# ArduinoUNOGamePlatform.net
KiCad netlist of a schematic drawn in EAGLE
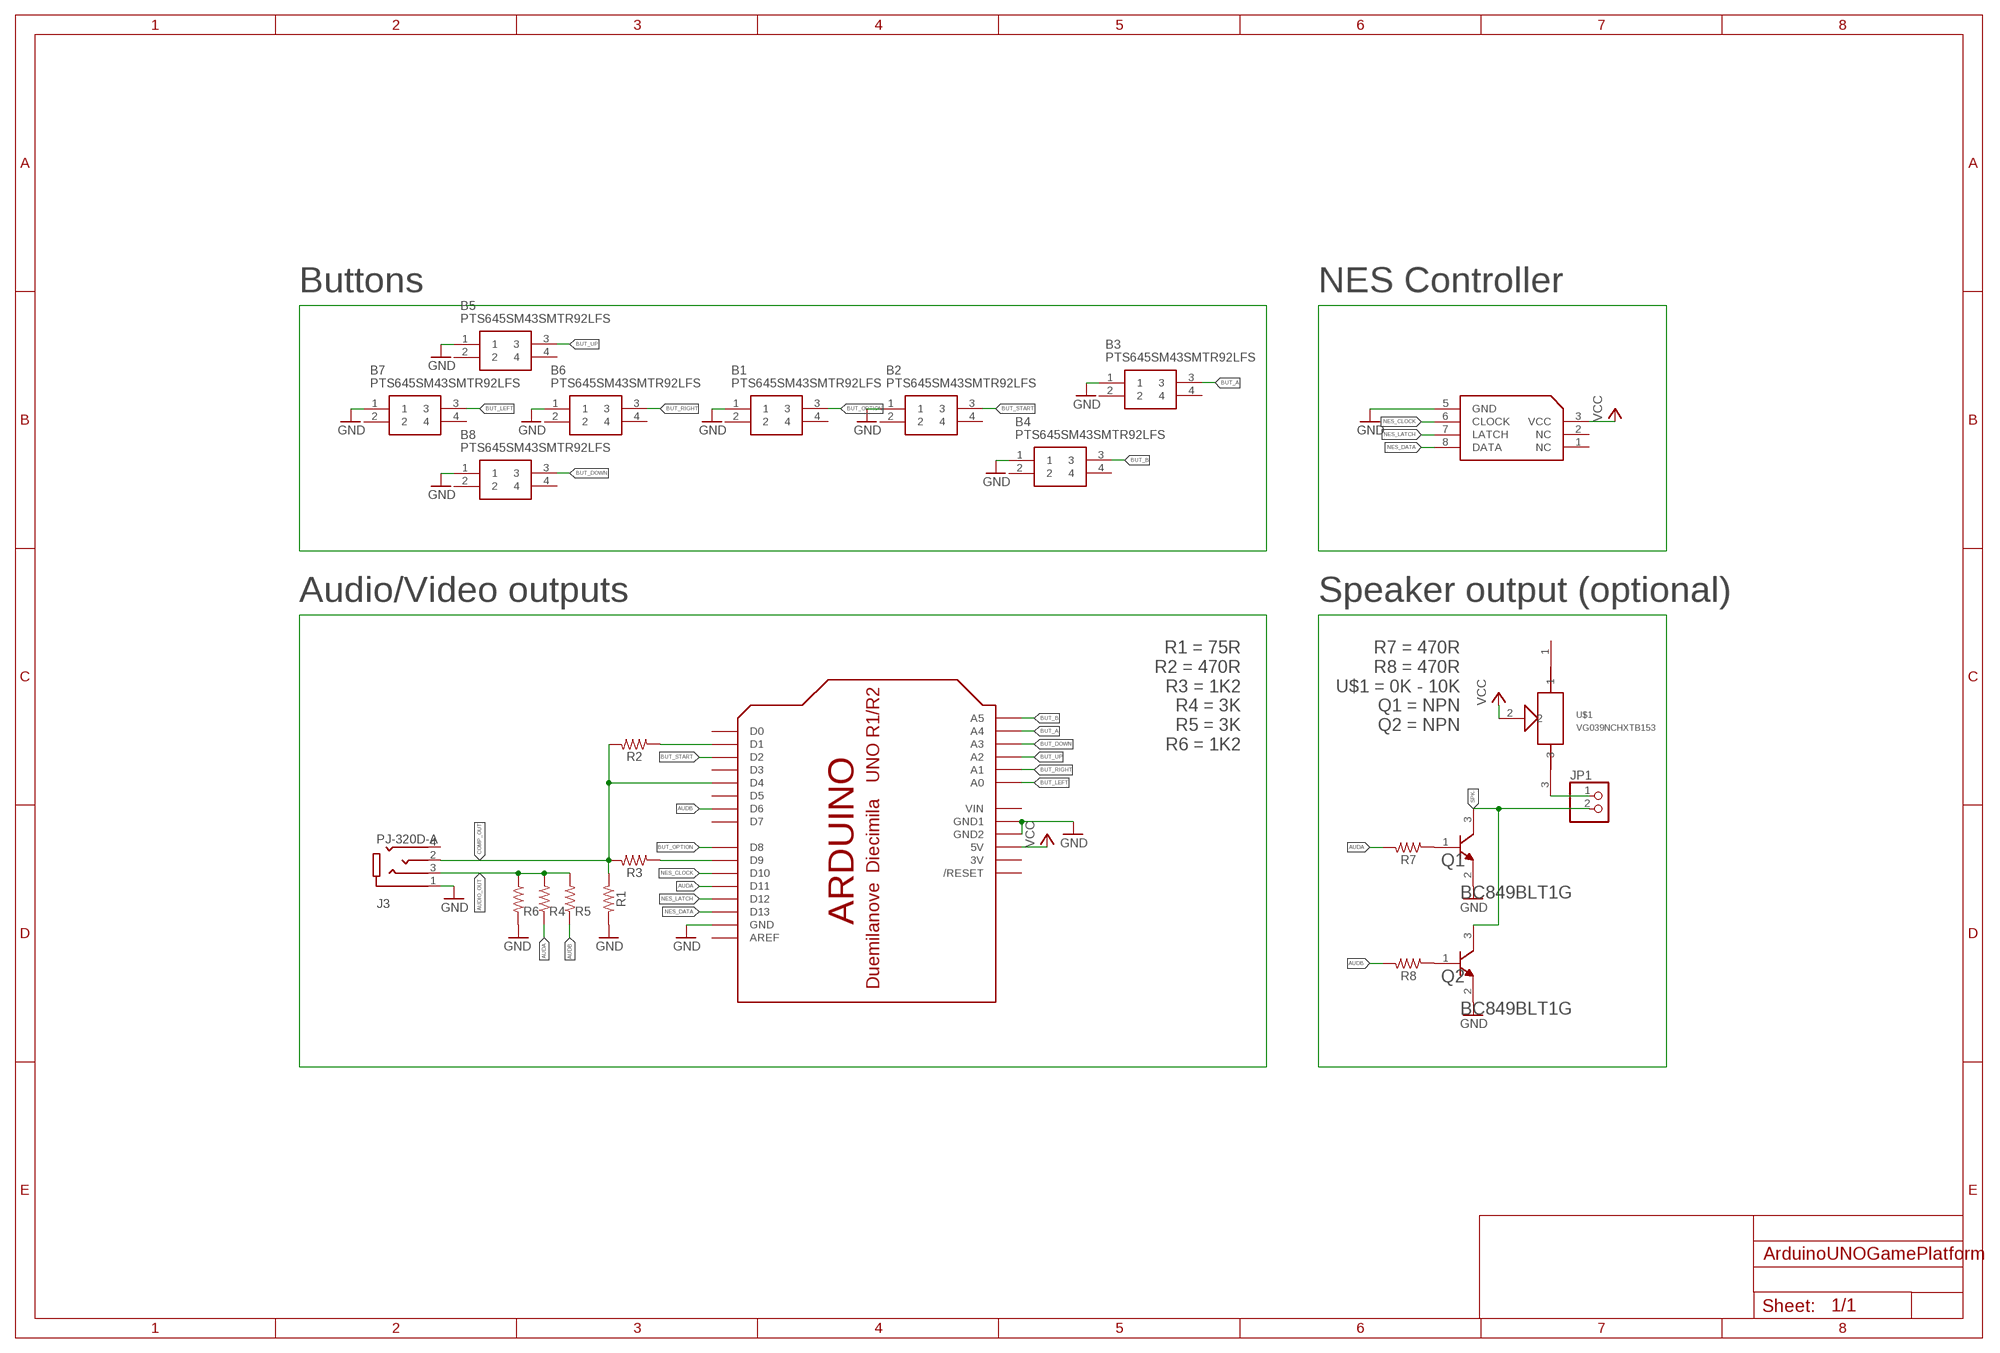
[diagram p0: schematic, sheet 1]

(export (version "E")
  (design (tool "Eeschema 10.0.6"))
  (components
    (comp (ref "B1")
      (value "PTS645SM43SMTR92LFS")
      (footprint "eagle-import:PTS645(SMT)")
      (fields (field (name "MOUSER_PART_NUMBER") "611-PTS645SM43SMTR92"))
      (libsource (lib "eagle-import") (part "PTS645SM43SMTR92LFS"))
    )
    (comp (ref "B2")
      (value "PTS645SM43SMTR92LFS")
      (footprint "eagle-import:PTS645(SMT)")
      (fields (field (name "MOUSER_PART_NUMBER") "611-PTS645SM43SMTR92"))
      (libsource (lib "eagle-import") (part "PTS645SM43SMTR92LFS"))
    )
    (comp (ref "B3")
      (value "PTS645SM43SMTR92LFS")
      (footprint "eagle-import:PTS645(SMT)")
      (fields (field (name "MOUSER_PART_NUMBER") "611-PTS645SM43SMTR92"))
      (libsource (lib "eagle-import") (part "PTS645SM43SMTR92LFS"))
    )
    (comp (ref "B4")
      (value "PTS645SM43SMTR92LFS")
      (footprint "eagle-import:PTS645(SMT)")
      (fields (field (name "MOUSER_PART_NUMBER") "611-PTS645SM43SMTR92"))
      (libsource (lib "eagle-import") (part "PTS645SM43SMTR92LFS"))
    )
    (comp (ref "B5")
      (value "PTS645SM43SMTR92LFS")
      (footprint "eagle-import:PTS645(SMT)")
      (fields (field (name "MOUSER_PART_NUMBER") "611-PTS645SM43SMTR92"))
      (libsource (lib "eagle-import") (part "PTS645SM43SMTR92LFS"))
    )
    (comp (ref "B6")
      (value "PTS645SM43SMTR92LFS")
      (footprint "eagle-import:PTS645(SMT)")
      (fields (field (name "MOUSER_PART_NUMBER") "611-PTS645SM43SMTR92"))
      (libsource (lib "eagle-import") (part "PTS645SM43SMTR92LFS"))
    )
    (comp (ref "B7")
      (value "PTS645SM43SMTR92LFS")
      (footprint "eagle-import:PTS645(SMT)")
      (fields (field (name "MOUSER_PART_NUMBER") "611-PTS645SM43SMTR92"))
      (libsource (lib "eagle-import") (part "PTS645SM43SMTR92LFS"))
    )
    (comp (ref "B8")
      (value "PTS645SM43SMTR92LFS")
      (footprint "eagle-import:PTS645(SMT)")
      (fields (field (name "MOUSER_PART_NUMBER") "611-PTS645SM43SMTR92"))
      (libsource (lib "eagle-import") (part "PTS645SM43SMTR92LFS"))
    )
    (comp (ref "J3")
      (value "PJ-320D-A")
      (footprint "eagle-import:HRO_PJ-320D-A")
      (fields (field (name "MF") "HRO Electronics Co., Ltd."))
      (libsource (lib "eagle-import") (part "PJ-320D-A"))
    )
    (comp (ref "JP1")
      (value "PINHD-1X2")
      (footprint "eagle-import:1X02")
      (libsource (lib "eagle-import") (part "PINHD-1X2"))
    )
    (comp (ref "Q1")
      (value "ON_SEMICONDUCTOR_BC849BLT1GON_SEMICONDUCTOR_BC849BLT1G_0_0")
      (footprint "eagle-import:ON_SEMICONDUCTOR_BC849BLT1G_0")
      (fields (field (name "MF") "On Semiconductor") (field (name "MPN") "BC849BLT1G"))
      (libsource (lib "eagle-import") (part "ON_SEMICONDUCTOR_BC849BLT1GON_SEMICONDUCTOR_BC849BLT1G_0_0"))
    )
    (comp (ref "Q2")
      (value "ON_SEMICONDUCTOR_BC849BLT1GON_SEMICONDUCTOR_BC849BLT1G_0_0")
      (footprint "eagle-import:ON_SEMICONDUCTOR_BC849BLT1G_0")
      (fields (field (name "MF") "On Semiconductor") (field (name "MPN") "BC849BLT1G"))
      (libsource (lib "eagle-import") (part "ON_SEMICONDUCTOR_BC849BLT1GON_SEMICONDUCTOR_BC849BLT1G_0_0"))
    )
    (comp (ref "R1")
      (value "75R")
      (footprint "eagle-import:52101-101-REV-A_RC-MASTER-SMD_R0603MP")
      (libsource (lib "eagle-import") (part "52101-101-REV-A_RC-MASTER-SMD_R_0603MP"))
    )
    (comp (ref "R2")
      (value "220R")
      (footprint "eagle-import:52101-101-REV-A_RC-MASTER-SMD_R0603MP")
      (libsource (lib "eagle-import") (part "52101-101-REV-A_RC-MASTER-SMD_R_0603MP"))
    )
    (comp (ref "R3")
      (value "1K2")
      (footprint "eagle-import:52101-101-REV-A_RC-MASTER-SMD_R0603MP")
      (libsource (lib "eagle-import") (part "52101-101-REV-A_RC-MASTER-SMD_R_0603MP"))
    )
    (comp (ref "R4")
      (value "3K")
      (footprint "eagle-import:52101-101-REV-A_RC-MASTER-SMD_R0603MP")
      (libsource (lib "eagle-import") (part "52101-101-REV-A_RC-MASTER-SMD_R_0603MP"))
    )
    (comp (ref "R5")
      (value "3K")
      (footprint "eagle-import:52101-101-REV-A_RC-MASTER-SMD_R0603MP")
      (libsource (lib "eagle-import") (part "52101-101-REV-A_RC-MASTER-SMD_R_0603MP"))
    )
    (comp (ref "R6")
      (value "1K2")
      (footprint "eagle-import:52101-101-REV-A_RC-MASTER-SMD_R0603MP")
      (libsource (lib "eagle-import") (part "52101-101-REV-A_RC-MASTER-SMD_R_0603MP"))
    )
    (comp (ref "R7")
      (value "470R")
      (footprint "eagle-import:52101-101-REV-A_RC-MASTER-SMD_R0603MP")
      (libsource (lib "eagle-import") (part "52101-101-REV-A_RC-MASTER-SMD_R_0603MP"))
    )
    (comp (ref "R8")
      (value "470R")
      (footprint "eagle-import:52101-101-REV-A_RC-MASTER-SMD_R0603MP")
      (libsource (lib "eagle-import") (part "52101-101-REV-A_RC-MASTER-SMD_R_0603MP"))
    )
    (comp (ref "U$1")
      (value "VG039NCHXTB153")
      (footprint "eagle-import:VG039NCHXTB101")
      (libsource (lib "eagle-import") (part "VG039NCHXTB153"))
    )
    (comp (ref "U$2")
      (value "ARDUINO-BPLACE")
      (footprint "eagle-import:ARDUINO-BPLACE")
      (libsource (lib "eagle-import") (part "ARDUINO-BPLACE"))
    )
    (comp (ref "U$3")
      (value "NES-CONTROLLER-PORT")
      (footprint "eagle-import:NES-CONTROLLER-SOCKET")
      (libsource (lib "eagle-import") (part "NES-CONTROLLER-PORT"))
    )
  )
  (nets
    (net (code "1") (name "/3V") (class "Default")
      (node (ref "U$2") (pin "3V") (pinfunction "3V_3V") (pintype "power_in"))
    )
    (net (code "2") (name "/VIN") (class "Default")
      (node (ref "U$2") (pin "VIN") (pinfunction "VIN_VIN") (pintype "power_in"))
    )
    (net (code "3") (name "AUDA") (class "Default")
      (node (ref "R4") (pin "1") (pinfunction "1_1") (pintype "passive"))
      (node (ref "R7") (pin "2") (pinfunction "2_2") (pintype "passive"))
      (node (ref "U$2") (pin "D11") (pinfunction "D11_D11") (pintype "bidirectional"))
    )
    (net (code "4") (name "AUDB") (class "Default")
      (node (ref "R5") (pin "1") (pinfunction "1_1") (pintype "passive"))
      (node (ref "R8") (pin "2") (pinfunction "2_2") (pintype "passive"))
      (node (ref "U$2") (pin "D6") (pinfunction "D6_D6") (pintype "bidirectional"))
    )
    (net (code "5") (name "AUDIO_OUT") (class "Default")
      (node (ref "J3") (pin "3") (pinfunction "RING1_3") (pintype "passive"))
      (node (ref "R4") (pin "2") (pinfunction "2_2") (pintype "passive"))
      (node (ref "R5") (pin "2") (pinfunction "2_2") (pintype "passive"))
      (node (ref "R6") (pin "1") (pinfunction "1_1") (pintype "passive"))
    )
    (net (code "6") (name "BUT_A") (class "Default")
      (node (ref "B3") (pin "3") (pinfunction "3_3") (pintype "bidirectional"))
      (node (ref "U$2") (pin "A4") (pinfunction "A4_A4") (pintype "bidirectional"))
    )
    (net (code "7") (name "BUT_B") (class "Default")
      (node (ref "B4") (pin "3") (pinfunction "3_3") (pintype "bidirectional"))
      (node (ref "U$2") (pin "A5") (pinfunction "A5_A5") (pintype "bidirectional"))
    )
    (net (code "8") (name "BUT_DOWN") (class "Default")
      (node (ref "B8") (pin "3") (pinfunction "3_3") (pintype "bidirectional"))
      (node (ref "U$2") (pin "A3") (pinfunction "A3_A3") (pintype "bidirectional"))
    )
    (net (code "9") (name "BUT_LEFT") (class "Default")
      (node (ref "B7") (pin "3") (pinfunction "3_3") (pintype "bidirectional"))
      (node (ref "U$2") (pin "A0") (pinfunction "A0_A0") (pintype "bidirectional"))
    )
    (net (code "10") (name "BUT_OPTION") (class "Default")
      (node (ref "B1") (pin "3") (pinfunction "3_3") (pintype "bidirectional"))
      (node (ref "U$2") (pin "D8") (pinfunction "D8_D8") (pintype "bidirectional"))
    )
    (net (code "11") (name "BUT_RIGHT") (class "Default")
      (node (ref "B6") (pin "3") (pinfunction "3_3") (pintype "bidirectional"))
      (node (ref "U$2") (pin "A1") (pinfunction "A1_A1") (pintype "bidirectional"))
    )
    (net (code "12") (name "BUT_START") (class "Default")
      (node (ref "B2") (pin "3") (pinfunction "3_3") (pintype "bidirectional"))
      (node (ref "U$2") (pin "D2") (pinfunction "D2_D2") (pintype "bidirectional"))
    )
    (net (code "13") (name "BUT_UP") (class "Default")
      (node (ref "B5") (pin "3") (pinfunction "3_3") (pintype "bidirectional"))
      (node (ref "U$2") (pin "A2") (pinfunction "A2_A2") (pintype "bidirectional"))
    )
    (net (code "14") (name "COMP_OUT") (class "Default")
      (node (ref "J3") (pin "2") (pinfunction "TIP_2") (pintype "passive"))
      (node (ref "R1") (pin "1") (pinfunction "1_1") (pintype "passive"))
      (node (ref "R2") (pin "2") (pinfunction "2_2") (pintype "passive"))
      (node (ref "R3") (pin "2") (pinfunction "2_2") (pintype "passive"))
      (node (ref "U$2") (pin "D4") (pinfunction "D4_D4") (pintype "bidirectional"))
    )
    (net (code "15") (name "GND") (class "Default")
      (node (ref "B1") (pin "1") (pinfunction "1_1") (pintype "bidirectional"))
      (node (ref "B2") (pin "1") (pinfunction "1_1") (pintype "bidirectional"))
      (node (ref "B3") (pin "1") (pinfunction "1_1") (pintype "bidirectional"))
      (node (ref "B4") (pin "1") (pinfunction "1_1") (pintype "bidirectional"))
      (node (ref "B5") (pin "1") (pinfunction "1_1") (pintype "bidirectional"))
      (node (ref "B6") (pin "1") (pinfunction "1_1") (pintype "bidirectional"))
      (node (ref "B7") (pin "1") (pinfunction "1_1") (pintype "bidirectional"))
      (node (ref "B8") (pin "1") (pinfunction "1_1") (pintype "bidirectional"))
      (node (ref "J3") (pin "1") (pinfunction "SLEEVE_1") (pintype "passive"))
      (node (ref "Q1") (pin "2") (pinfunction "E_2") (pintype "passive"))
      (node (ref "Q2") (pin "2") (pinfunction "E_2") (pintype "passive"))
      (node (ref "R1") (pin "2") (pinfunction "2_2") (pintype "passive"))
      (node (ref "R6") (pin "2") (pinfunction "2_2") (pintype "passive"))
      (node (ref "U$2") (pin "GND") (pinfunction "GND_GND") (pintype "power_in"))
      (node (ref "U$2") (pin "GND1") (pinfunction "GND1_GND1") (pintype "power_in"))
      (node (ref "U$2") (pin "GND2") (pinfunction "GND2_GND2") (pintype "power_in"))
      (node (ref "U$3") (pin "5") (pinfunction "GND_5") (pintype "bidirectional"))
    )
    (net (code "16") (name "NES_CLOCK") (class "Default")
      (node (ref "U$2") (pin "D10") (pinfunction "D10_D10") (pintype "bidirectional"))
      (node (ref "U$3") (pin "6") (pinfunction "CLOCK_6") (pintype "bidirectional"))
    )
    (net (code "17") (name "NES_DATA") (class "Default")
      (node (ref "U$2") (pin "D13") (pinfunction "D13_D13") (pintype "bidirectional"))
      (node (ref "U$3") (pin "8") (pinfunction "DATA_8") (pintype "bidirectional"))
    )
    (net (code "18") (name "NES_LATCH") (class "Default")
      (node (ref "U$2") (pin "D12") (pinfunction "D12_D12") (pintype "bidirectional"))
      (node (ref "U$3") (pin "7") (pinfunction "LATCH_7") (pintype "bidirectional"))
    )
    (net (code "19") (name "Net-(JP1-Pad1)") (class "Default")
      (node (ref "JP1") (pin "1") (pinfunction "1_1") (pintype "passive"))
      (node (ref "U$1") (pin "3") (pinfunction "3_3") (pintype "bidirectional"))
    )
    (net (code "20") (name "Net-(Q1-B)") (class "Default")
      (node (ref "Q1") (pin "1") (pinfunction "B_1") (pintype "passive"))
      (node (ref "R7") (pin "1") (pinfunction "1_1") (pintype "passive"))
    )
    (net (code "21") (name "Net-(Q2-B)") (class "Default")
      (node (ref "Q2") (pin "1") (pinfunction "B_1") (pintype "passive"))
      (node (ref "R8") (pin "1") (pinfunction "1_1") (pintype "passive"))
    )
    (net (code "22") (name "Net-(R2-Pad1)") (class "Default")
      (node (ref "R2") (pin "1") (pinfunction "1_1") (pintype "passive"))
      (node (ref "U$2") (pin "D1") (pinfunction "D1_D1") (pintype "bidirectional"))
    )
    (net (code "23") (name "Net-(R3-Pad1)") (class "Default")
      (node (ref "R3") (pin "1") (pinfunction "1_1") (pintype "passive"))
      (node (ref "U$2") (pin "D9") (pinfunction "D9_D9") (pintype "bidirectional"))
    )
    (net (code "24") (name "SPK-") (class "Default")
      (node (ref "JP1") (pin "2") (pinfunction "2_2") (pintype "passive"))
      (node (ref "Q1") (pin "3") (pinfunction "C_3") (pintype "passive"))
      (node (ref "Q2") (pin "3") (pinfunction "C_3") (pintype "passive"))
    )
    (net (code "25") (name "VCC") (class "Default")
      (node (ref "U$1") (pin "2") (pinfunction "2_2") (pintype "bidirectional"))
      (node (ref "U$2") (pin "5V") (pinfunction "5V_5V") (pintype "power_in"))
      (node (ref "U$3") (pin "3") (pinfunction "VCC_3") (pintype "bidirectional"))
    )
    (net (code "26") (name "unconnected-(B1-Pad2)") (class "Default")
      (node (ref "B1") (pin "2") (pinfunction "2_2") (pintype "bidirectional"))
    )
    (net (code "27") (name "unconnected-(B1-Pad4)") (class "Default")
      (node (ref "B1") (pin "4") (pinfunction "4_4") (pintype "bidirectional"))
    )
    (net (code "28") (name "unconnected-(B2-Pad2)") (class "Default")
      (node (ref "B2") (pin "2") (pinfunction "2_2") (pintype "bidirectional"))
    )
    (net (code "29") (name "unconnected-(B2-Pad4)") (class "Default")
      (node (ref "B2") (pin "4") (pinfunction "4_4") (pintype "bidirectional"))
    )
    (net (code "30") (name "unconnected-(B3-Pad2)") (class "Default")
      (node (ref "B3") (pin "2") (pinfunction "2_2") (pintype "bidirectional"))
    )
    (net (code "31") (name "unconnected-(B3-Pad4)") (class "Default")
      (node (ref "B3") (pin "4") (pinfunction "4_4") (pintype "bidirectional"))
    )
    (net (code "32") (name "unconnected-(B4-Pad2)") (class "Default")
      (node (ref "B4") (pin "2") (pinfunction "2_2") (pintype "bidirectional"))
    )
    (net (code "33") (name "unconnected-(B4-Pad4)") (class "Default")
      (node (ref "B4") (pin "4") (pinfunction "4_4") (pintype "bidirectional"))
    )
    (net (code "34") (name "unconnected-(B5-Pad2)") (class "Default")
      (node (ref "B5") (pin "2") (pinfunction "2_2") (pintype "bidirectional"))
    )
    (net (code "35") (name "unconnected-(B5-Pad4)") (class "Default")
      (node (ref "B5") (pin "4") (pinfunction "4_4") (pintype "bidirectional"))
    )
    (net (code "36") (name "unconnected-(B6-Pad2)") (class "Default")
      (node (ref "B6") (pin "2") (pinfunction "2_2") (pintype "bidirectional"))
    )
    (net (code "37") (name "unconnected-(B6-Pad4)") (class "Default")
      (node (ref "B6") (pin "4") (pinfunction "4_4") (pintype "bidirectional"))
    )
    (net (code "38") (name "unconnected-(B7-Pad2)") (class "Default")
      (node (ref "B7") (pin "2") (pinfunction "2_2") (pintype "bidirectional"))
    )
    (net (code "39") (name "unconnected-(B7-Pad4)") (class "Default")
      (node (ref "B7") (pin "4") (pinfunction "4_4") (pintype "bidirectional"))
    )
    (net (code "40") (name "unconnected-(B8-Pad2)") (class "Default")
      (node (ref "B8") (pin "2") (pinfunction "2_2") (pintype "bidirectional"))
    )
    (net (code "41") (name "unconnected-(B8-Pad4)") (class "Default")
      (node (ref "B8") (pin "4") (pinfunction "4_4") (pintype "bidirectional"))
    )
    (net (code "42") (name "unconnected-(J3-RING2-Pad4)") (class "Default")
      (node (ref "J3") (pin "4") (pinfunction "RING2_4") (pintype "passive"))
    )
    (net (code "43") (name "unconnected-(U$1-Pad1)") (class "Default")
      (node (ref "U$1") (pin "1") (pinfunction "1_1") (pintype "bidirectional"))
    )
    (net (code "44") (name "unconnected-(U$2-PadAREF)") (class "Default")
      (node (ref "U$2") (pin "AREF") (pinfunction "AREF_AREF") (pintype "bidirectional"))
    )
    (net (code "45") (name "unconnected-(U$2-PadD0)") (class "Default")
      (node (ref "U$2") (pin "D0") (pinfunction "D0_D0") (pintype "bidirectional"))
    )
    (net (code "46") (name "unconnected-(U$2-PadD3)") (class "Default")
      (node (ref "U$2") (pin "D3") (pinfunction "D3_D3") (pintype "bidirectional"))
    )
    (net (code "47") (name "unconnected-(U$2-PadD5)") (class "Default")
      (node (ref "U$2") (pin "D5") (pinfunction "D5_D5") (pintype "bidirectional"))
    )
    (net (code "48") (name "unconnected-(U$2-PadD7)") (class "Default")
      (node (ref "U$2") (pin "D7") (pinfunction "D7_D7") (pintype "bidirectional"))
    )
    (net (code "49") (name "unconnected-(U$2-{slash}RESET-PadRESET)") (class "Default")
      (node (ref "U$2") (pin "RESET") (pinfunction "/RESET_RESET") (pintype "bidirectional"))
    )
    (net (code "50") (name "unconnected-(U$3-NC-Pad1)") (class "Default")
      (node (ref "U$3") (pin "1") (pinfunction "NC_1") (pintype "bidirectional"))
    )
    (net (code "51") (name "unconnected-(U$3-NC-Pad2)") (class "Default")
      (node (ref "U$3") (pin "2") (pinfunction "NC_2") (pintype "bidirectional"))
    )
  )
)
